# dual_seq_v1_0_0_pnl.net
KiCad netlist of a schematic drawn in EAGLE
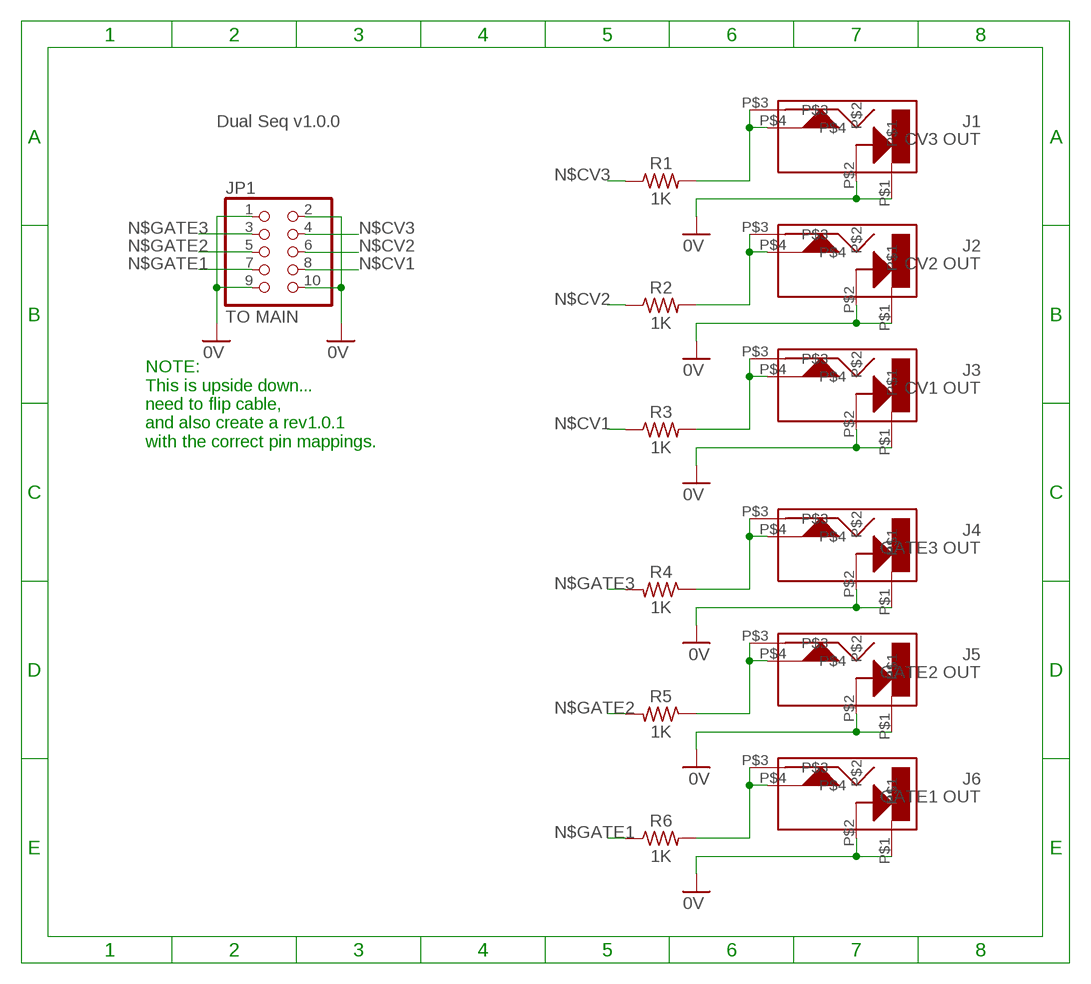
[diagram p0: schematic, sheet 1]

(export (version "E")
  (design (tool "Eeschema 10.0.6"))
  (components
    (comp (ref "J1")
      (value "CV3 OUT")
      (footprint "eagle-import:CL1384")
      (libsource (lib "eagle-import") (part "CL1384"))
    )
    (comp (ref "J2")
      (value "CV2 OUT")
      (footprint "eagle-import:CL1384")
      (libsource (lib "eagle-import") (part "CL1384"))
    )
    (comp (ref "J3")
      (value "CV1 OUT")
      (footprint "eagle-import:CL1384")
      (libsource (lib "eagle-import") (part "CL1384"))
    )
    (comp (ref "J4")
      (value "GATE3 OUT")
      (footprint "eagle-import:CL1384")
      (libsource (lib "eagle-import") (part "CL1384"))
    )
    (comp (ref "J5")
      (value "GATE2 OUT")
      (footprint "eagle-import:CL1384")
      (libsource (lib "eagle-import") (part "CL1384"))
    )
    (comp (ref "J6")
      (value "GATE1 OUT")
      (footprint "eagle-import:CL1384")
      (libsource (lib "eagle-import") (part "CL1384"))
    )
    (comp (ref "JP1")
      (value "TO MAIN")
      (footprint "eagle-import:2X05")
      (libsource (lib "eagle-import") (part "PINHD-2X5"))
    )
    (comp (ref "R1")
      (value "1K")
      (footprint "eagle-import:0207_7")
      (libsource (lib "eagle-import") (part "R"))
    )
    (comp (ref "R2")
      (value "1K")
      (footprint "eagle-import:0207_7")
      (libsource (lib "eagle-import") (part "R"))
    )
    (comp (ref "R3")
      (value "1K")
      (footprint "eagle-import:0207_7")
      (libsource (lib "eagle-import") (part "R"))
    )
    (comp (ref "R4")
      (value "1K")
      (footprint "eagle-import:0207_7")
      (libsource (lib "eagle-import") (part "R"))
    )
    (comp (ref "R5")
      (value "1K")
      (footprint "eagle-import:0207_7")
      (libsource (lib "eagle-import") (part "R"))
    )
    (comp (ref "R6")
      (value "1K")
      (footprint "eagle-import:0207_7")
      (libsource (lib "eagle-import") (part "R"))
    )
  )
  (nets
    (net (code "1") (name "/N$CV1") (class "Default")
      (node (ref "JP1") (pin "8") (pinfunction "8_8") (pintype "passive"))
      (node (ref "R3") (pin "1") (pinfunction "1_1") (pintype "passive"))
    )
    (net (code "2") (name "/N$CV2") (class "Default")
      (node (ref "JP1") (pin "6") (pinfunction "6_6") (pintype "passive"))
      (node (ref "R2") (pin "1") (pinfunction "1_1") (pintype "passive"))
    )
    (net (code "3") (name "/N$CV3") (class "Default")
      (node (ref "JP1") (pin "4") (pinfunction "4_4") (pintype "passive"))
      (node (ref "R1") (pin "1") (pinfunction "1_1") (pintype "passive"))
    )
    (net (code "4") (name "/N$GATE1") (class "Default")
      (node (ref "JP1") (pin "7") (pinfunction "7_7") (pintype "passive"))
      (node (ref "R6") (pin "1") (pinfunction "1_1") (pintype "passive"))
    )
    (net (code "5") (name "/N$GATE2") (class "Default")
      (node (ref "JP1") (pin "5") (pinfunction "5_5") (pintype "passive"))
      (node (ref "R5") (pin "2") (pinfunction "2_2") (pintype "passive"))
    )
    (net (code "6") (name "/N$GATE3") (class "Default")
      (node (ref "JP1") (pin "3") (pinfunction "3_3") (pintype "passive"))
      (node (ref "R4") (pin "2") (pinfunction "2_2") (pintype "passive"))
    )
    (net (code "7") (name "0V") (class "Default")
      (node (ref "J1") (pin "P$1") (pinfunction "P$1_P$1") (pintype "bidirectional"))
      (node (ref "J1") (pin "P$2") (pinfunction "P$2_P$2") (pintype "bidirectional"))
      (node (ref "J2") (pin "P$1") (pinfunction "P$1_P$1") (pintype "bidirectional"))
      (node (ref "J2") (pin "P$2") (pinfunction "P$2_P$2") (pintype "bidirectional"))
      (node (ref "J3") (pin "P$1") (pinfunction "P$1_P$1") (pintype "bidirectional"))
      (node (ref "J3") (pin "P$2") (pinfunction "P$2_P$2") (pintype "bidirectional"))
      (node (ref "J4") (pin "P$1") (pinfunction "P$1_P$1") (pintype "bidirectional"))
      (node (ref "J4") (pin "P$2") (pinfunction "P$2_P$2") (pintype "bidirectional"))
      (node (ref "J5") (pin "P$1") (pinfunction "P$1_P$1") (pintype "bidirectional"))
      (node (ref "J5") (pin "P$2") (pinfunction "P$2_P$2") (pintype "bidirectional"))
      (node (ref "J6") (pin "P$1") (pinfunction "P$1_P$1") (pintype "bidirectional"))
      (node (ref "J6") (pin "P$2") (pinfunction "P$2_P$2") (pintype "bidirectional"))
      (node (ref "JP1") (pin "1") (pinfunction "1_1") (pintype "passive"))
      (node (ref "JP1") (pin "10") (pinfunction "10_10") (pintype "passive"))
      (node (ref "JP1") (pin "2") (pinfunction "2_2") (pintype "passive"))
      (node (ref "JP1") (pin "9") (pinfunction "9_9") (pintype "passive"))
    )
    (net (code "8") (name "Net-(J1-PadP$3)") (class "Default")
      (node (ref "J1") (pin "P$3") (pinfunction "P$3_P$3") (pintype "bidirectional"))
      (node (ref "J1") (pin "P$4") (pinfunction "P$4_P$4") (pintype "bidirectional"))
      (node (ref "R1") (pin "2") (pinfunction "2_2") (pintype "passive"))
    )
    (net (code "9") (name "Net-(J2-PadP$3)") (class "Default")
      (node (ref "J2") (pin "P$3") (pinfunction "P$3_P$3") (pintype "bidirectional"))
      (node (ref "J2") (pin "P$4") (pinfunction "P$4_P$4") (pintype "bidirectional"))
      (node (ref "R2") (pin "2") (pinfunction "2_2") (pintype "passive"))
    )
    (net (code "10") (name "Net-(J3-PadP$3)") (class "Default")
      (node (ref "J3") (pin "P$3") (pinfunction "P$3_P$3") (pintype "bidirectional"))
      (node (ref "J3") (pin "P$4") (pinfunction "P$4_P$4") (pintype "bidirectional"))
      (node (ref "R3") (pin "2") (pinfunction "2_2") (pintype "passive"))
    )
    (net (code "11") (name "Net-(J4-PadP$3)") (class "Default")
      (node (ref "J4") (pin "P$3") (pinfunction "P$3_P$3") (pintype "bidirectional"))
      (node (ref "J4") (pin "P$4") (pinfunction "P$4_P$4") (pintype "bidirectional"))
      (node (ref "R4") (pin "1") (pinfunction "1_1") (pintype "passive"))
    )
    (net (code "12") (name "Net-(J5-PadP$3)") (class "Default")
      (node (ref "J5") (pin "P$3") (pinfunction "P$3_P$3") (pintype "bidirectional"))
      (node (ref "J5") (pin "P$4") (pinfunction "P$4_P$4") (pintype "bidirectional"))
      (node (ref "R5") (pin "1") (pinfunction "1_1") (pintype "passive"))
    )
    (net (code "13") (name "Net-(J6-PadP$3)") (class "Default")
      (node (ref "J6") (pin "P$3") (pinfunction "P$3_P$3") (pintype "bidirectional"))
      (node (ref "J6") (pin "P$4") (pinfunction "P$4_P$4") (pintype "bidirectional"))
      (node (ref "R6") (pin "2") (pinfunction "2_2") (pintype "passive"))
    )
  )
)
